# uOsc_2_board_1_v2_0.net
KiCad netlist of a schematic drawn in EAGLE
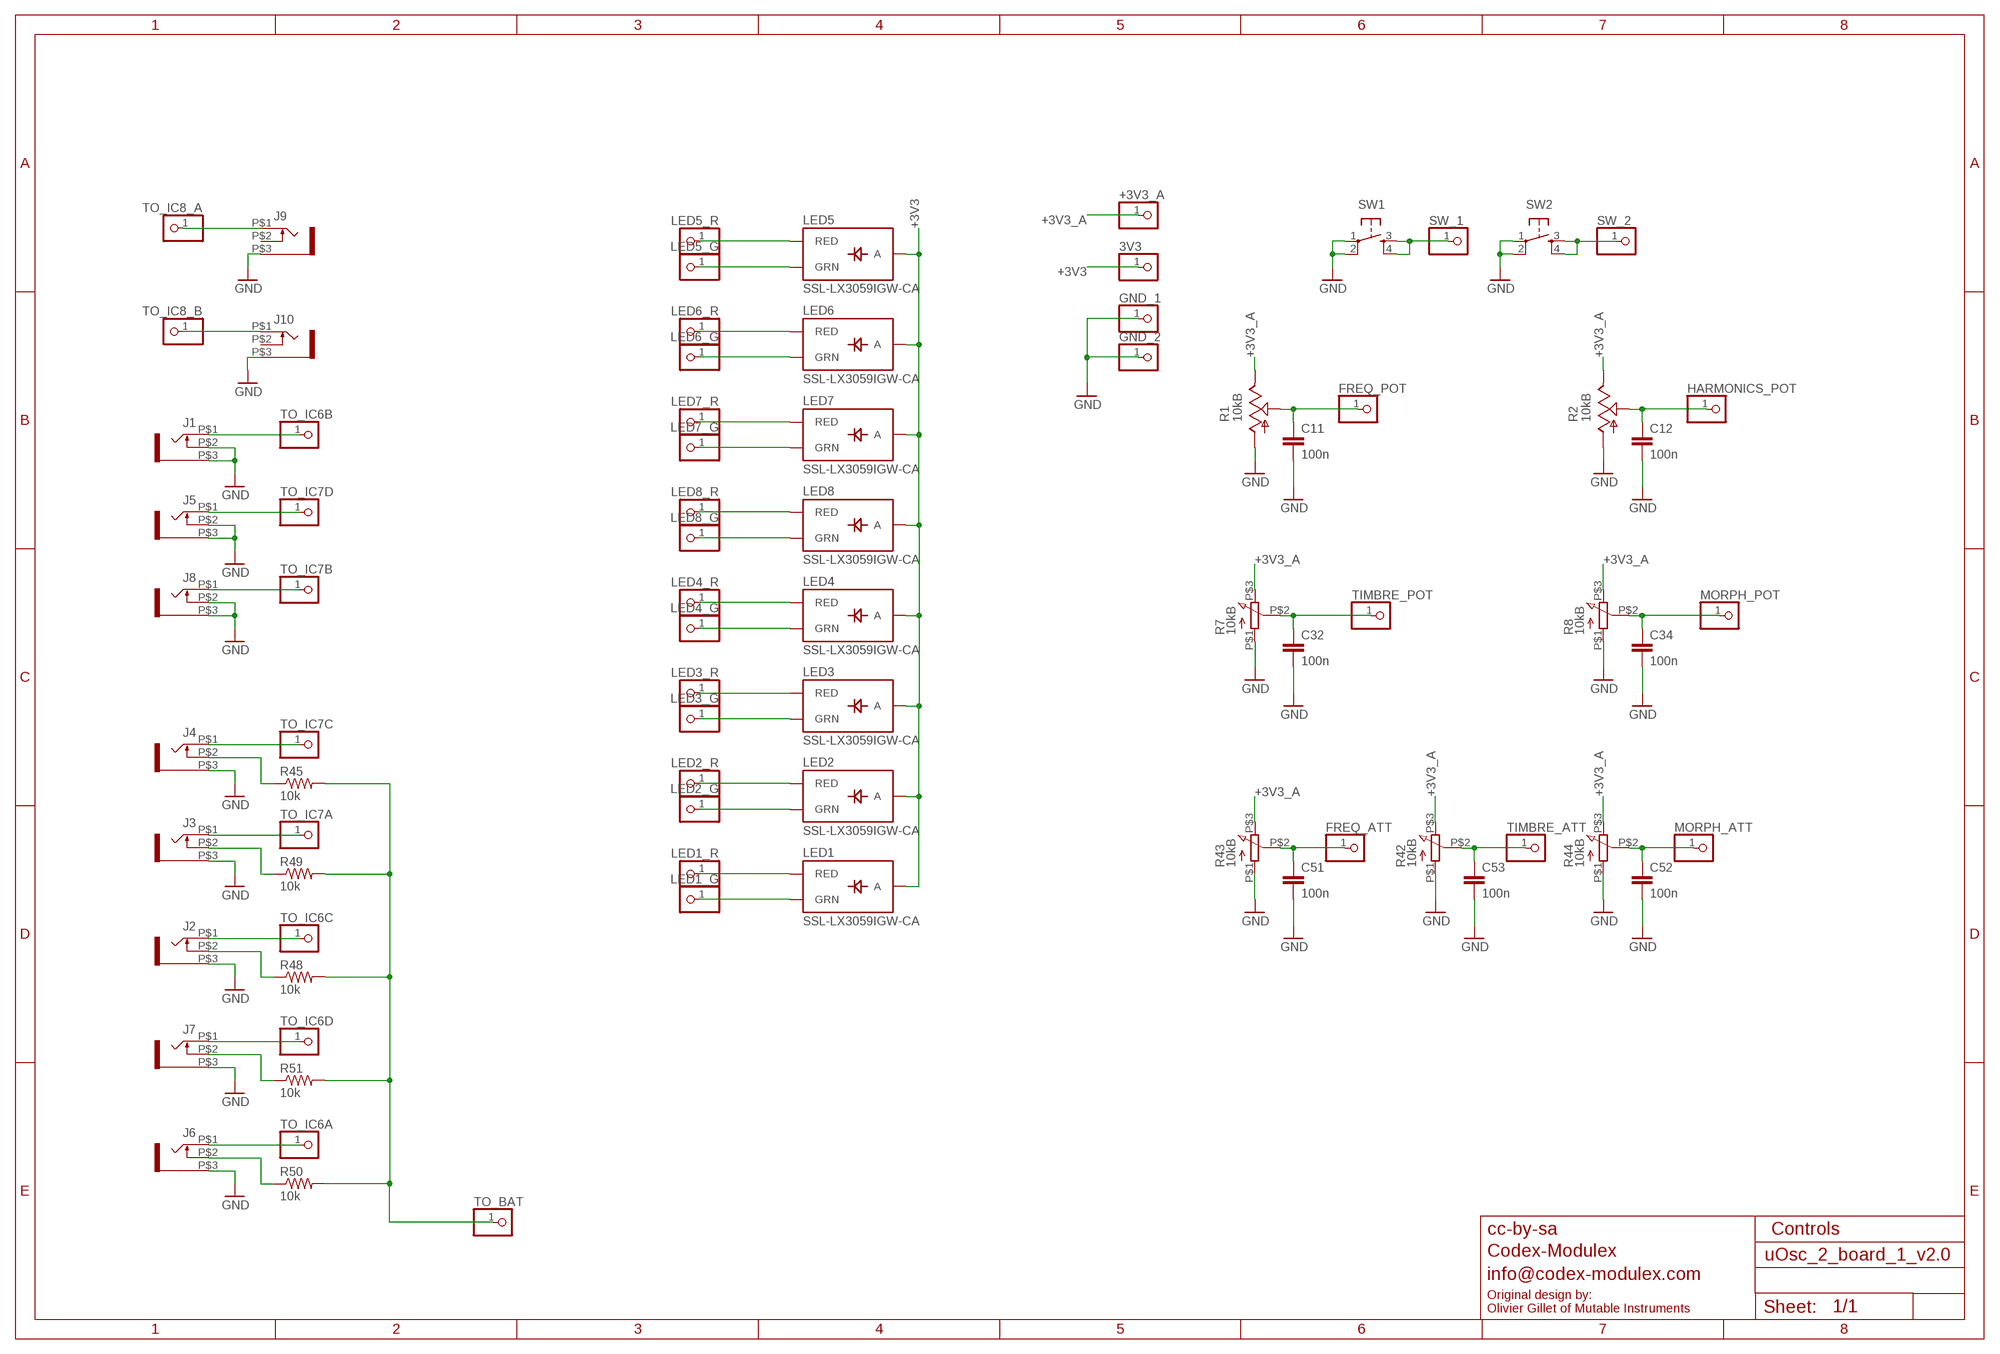
[diagram p0: schematic, sheet 1]

(export (version "E")
  (design (tool "Eeschema 10.0.6"))
  (components
    (comp (ref "+3V3_A")
      (value "PARTS_AMAN_PINHD-1X1")
      (footprint "eagle-import:PARTS_AMAN_1X01")
      (libsource (lib "eagle-import") (part "PARTS_AMAN_PINHD-1X1"))
    )
    (comp (ref "3V3")
      (value "PARTS_AMAN_PINHD-1X1")
      (footprint "eagle-import:PARTS_AMAN_1X01")
      (libsource (lib "eagle-import") (part "PARTS_AMAN_PINHD-1X1"))
    )
    (comp (ref "C11")
      (value "100n")
      (footprint "eagle-import:PARTS_AMAN_RESISTOR_0603")
      (libsource (lib "eagle-import") (part "PARTS_AMAN_CAPACITOR"))
    )
    (comp (ref "C12")
      (value "100n")
      (footprint "eagle-import:PARTS_AMAN_RESISTOR_0603")
      (libsource (lib "eagle-import") (part "PARTS_AMAN_CAPACITOR"))
    )
    (comp (ref "C32")
      (value "100n")
      (footprint "eagle-import:PARTS_AMAN_RESISTOR_0603")
      (libsource (lib "eagle-import") (part "PARTS_AMAN_CAPACITOR"))
    )
    (comp (ref "C34")
      (value "100n")
      (footprint "eagle-import:PARTS_AMAN_RESISTOR_0603")
      (libsource (lib "eagle-import") (part "PARTS_AMAN_CAPACITOR"))
    )
    (comp (ref "C51")
      (value "100n")
      (footprint "eagle-import:PARTS_AMAN_RESISTOR_0603")
      (libsource (lib "eagle-import") (part "PARTS_AMAN_CAPACITOR"))
    )
    (comp (ref "C52")
      (value "100n")
      (footprint "eagle-import:PARTS_AMAN_RESISTOR_0603")
      (libsource (lib "eagle-import") (part "PARTS_AMAN_CAPACITOR"))
    )
    (comp (ref "C53")
      (value "100n")
      (footprint "eagle-import:PARTS_AMAN_RESISTOR_0603")
      (libsource (lib "eagle-import") (part "PARTS_AMAN_CAPACITOR"))
    )
    (comp (ref "FREQ_ATT")
      (value "PARTS_AMAN_PINHD-1X1")
      (footprint "eagle-import:PARTS_AMAN_1X01")
      (libsource (lib "eagle-import") (part "PARTS_AMAN_PINHD-1X1"))
    )
    (comp (ref "FREQ_POT")
      (value "PARTS_AMAN_PINHD-1X1")
      (footprint "eagle-import:PARTS_AMAN_1X01")
      (libsource (lib "eagle-import") (part "PARTS_AMAN_PINHD-1X1"))
    )
    (comp (ref "GND_1")
      (value "PARTS_AMAN_PINHD-1X1")
      (footprint "eagle-import:PARTS_AMAN_1X01")
      (libsource (lib "eagle-import") (part "PARTS_AMAN_PINHD-1X1"))
    )
    (comp (ref "GND_2")
      (value "PARTS_AMAN_PINHD-1X1")
      (footprint "eagle-import:PARTS_AMAN_1X01")
      (libsource (lib "eagle-import") (part "PARTS_AMAN_PINHD-1X1"))
    )
    (comp (ref "HARMONICS_POT")
      (value "PARTS_AMAN_PINHD-1X1")
      (footprint "eagle-import:PARTS_AMAN_1X01")
      (libsource (lib "eagle-import") (part "PARTS_AMAN_PINHD-1X1"))
    )
    (comp (ref "J1")
      (value "WQP-PJ301M-12_JACK")
      (footprint "eagle-import:WQP-PJ301M-12_JACK")
      (libsource (lib "eagle-import") (part "WQP-PJ301M-12_JACK"))
    )
    (comp (ref "J2")
      (value "WQP-PJ301M-12_JACK")
      (footprint "eagle-import:WQP-PJ301M-12_JACK")
      (libsource (lib "eagle-import") (part "WQP-PJ301M-12_JACK"))
    )
    (comp (ref "J3")
      (value "WQP-PJ301M-12_JACK")
      (footprint "eagle-import:WQP-PJ301M-12_JACK")
      (libsource (lib "eagle-import") (part "WQP-PJ301M-12_JACK"))
    )
    (comp (ref "J4")
      (value "WQP-PJ301M-12_JACK")
      (footprint "eagle-import:WQP-PJ301M-12_JACK")
      (libsource (lib "eagle-import") (part "WQP-PJ301M-12_JACK"))
    )
    (comp (ref "J5")
      (value "WQP-PJ301M-12_JACK")
      (footprint "eagle-import:WQP-PJ301M-12_JACK")
      (libsource (lib "eagle-import") (part "WQP-PJ301M-12_JACK"))
    )
    (comp (ref "J6")
      (value "WQP-PJ301M-12_JACK")
      (footprint "eagle-import:WQP-PJ301M-12_JACK")
      (libsource (lib "eagle-import") (part "WQP-PJ301M-12_JACK"))
    )
    (comp (ref "J7")
      (value "WQP-PJ301M-12_JACK")
      (footprint "eagle-import:WQP-PJ301M-12_JACK")
      (libsource (lib "eagle-import") (part "WQP-PJ301M-12_JACK"))
    )
    (comp (ref "J8")
      (value "WQP-PJ301M-12_JACK")
      (footprint "eagle-import:WQP-PJ301M-12_JACK")
      (libsource (lib "eagle-import") (part "WQP-PJ301M-12_JACK"))
    )
    (comp (ref "J9")
      (value "WQP-PJ301M-12_JACK")
      (footprint "eagle-import:WQP-PJ301M-12_JACK")
      (libsource (lib "eagle-import") (part "WQP-PJ301M-12_JACK"))
    )
    (comp (ref "J10")
      (value "WQP-PJ301M-12_JACK")
      (footprint "eagle-import:WQP-PJ301M-12_JACK")
      (libsource (lib "eagle-import") (part "WQP-PJ301M-12_JACK"))
    )
    (comp (ref "LED1")
      (value "SSL-LX3059IGW-CA")
      (footprint "eagle-import:LED-BICOLOR-THROUGHHOLE-LUMEX")
      (libsource (lib "eagle-import") (part "LED-BICOLOR-THROUGHHOLE-CA"))
    )
    (comp (ref "LED1_G")
      (value "PARTS_AMAN_PINHD-1X1")
      (footprint "eagle-import:PARTS_AMAN_1X01")
      (libsource (lib "eagle-import") (part "PARTS_AMAN_PINHD-1X1"))
    )
    (comp (ref "LED1_R")
      (value "PARTS_AMAN_PINHD-1X1")
      (footprint "eagle-import:PARTS_AMAN_1X01")
      (libsource (lib "eagle-import") (part "PARTS_AMAN_PINHD-1X1"))
    )
    (comp (ref "LED2")
      (value "SSL-LX3059IGW-CA")
      (footprint "eagle-import:LED-BICOLOR-THROUGHHOLE-LUMEX")
      (libsource (lib "eagle-import") (part "LED-BICOLOR-THROUGHHOLE-CA"))
    )
    (comp (ref "LED2_G")
      (value "PARTS_AMAN_PINHD-1X1")
      (footprint "eagle-import:PARTS_AMAN_1X01")
      (libsource (lib "eagle-import") (part "PARTS_AMAN_PINHD-1X1"))
    )
    (comp (ref "LED2_R")
      (value "PARTS_AMAN_PINHD-1X1")
      (footprint "eagle-import:PARTS_AMAN_1X01")
      (libsource (lib "eagle-import") (part "PARTS_AMAN_PINHD-1X1"))
    )
    (comp (ref "LED3")
      (value "SSL-LX3059IGW-CA")
      (footprint "eagle-import:LED-BICOLOR-THROUGHHOLE-LUMEX")
      (libsource (lib "eagle-import") (part "LED-BICOLOR-THROUGHHOLE-CA"))
    )
    (comp (ref "LED3_G")
      (value "PARTS_AMAN_PINHD-1X1")
      (footprint "eagle-import:PARTS_AMAN_1X01")
      (libsource (lib "eagle-import") (part "PARTS_AMAN_PINHD-1X1"))
    )
    (comp (ref "LED3_R")
      (value "PARTS_AMAN_PINHD-1X1")
      (footprint "eagle-import:PARTS_AMAN_1X01")
      (libsource (lib "eagle-import") (part "PARTS_AMAN_PINHD-1X1"))
    )
    (comp (ref "LED4")
      (value "SSL-LX3059IGW-CA")
      (footprint "eagle-import:LED-BICOLOR-THROUGHHOLE-LUMEX")
      (libsource (lib "eagle-import") (part "LED-BICOLOR-THROUGHHOLE-CA"))
    )
    (comp (ref "LED4_G")
      (value "PARTS_AMAN_PINHD-1X1")
      (footprint "eagle-import:PARTS_AMAN_1X01")
      (libsource (lib "eagle-import") (part "PARTS_AMAN_PINHD-1X1"))
    )
    (comp (ref "LED4_R")
      (value "PARTS_AMAN_PINHD-1X1")
      (footprint "eagle-import:PARTS_AMAN_1X01")
      (libsource (lib "eagle-import") (part "PARTS_AMAN_PINHD-1X1"))
    )
    (comp (ref "LED5")
      (value "SSL-LX3059IGW-CA")
      (footprint "eagle-import:LED-BICOLOR-THROUGHHOLE-LUMEX")
      (libsource (lib "eagle-import") (part "LED-BICOLOR-THROUGHHOLE-CA"))
    )
    (comp (ref "LED5_G")
      (value "PARTS_AMAN_PINHD-1X1")
      (footprint "eagle-import:PARTS_AMAN_1X01")
      (libsource (lib "eagle-import") (part "PARTS_AMAN_PINHD-1X1"))
    )
    (comp (ref "LED5_R")
      (value "PARTS_AMAN_PINHD-1X1")
      (footprint "eagle-import:PARTS_AMAN_1X01")
      (libsource (lib "eagle-import") (part "PARTS_AMAN_PINHD-1X1"))
    )
    (comp (ref "LED6")
      (value "SSL-LX3059IGW-CA")
      (footprint "eagle-import:LED-BICOLOR-THROUGHHOLE-LUMEX")
      (libsource (lib "eagle-import") (part "LED-BICOLOR-THROUGHHOLE-CA"))
    )
    (comp (ref "LED6_G")
      (value "PARTS_AMAN_PINHD-1X1")
      (footprint "eagle-import:PARTS_AMAN_1X01")
      (libsource (lib "eagle-import") (part "PARTS_AMAN_PINHD-1X1"))
    )
    (comp (ref "LED6_R")
      (value "PARTS_AMAN_PINHD-1X1")
      (footprint "eagle-import:PARTS_AMAN_1X01")
      (libsource (lib "eagle-import") (part "PARTS_AMAN_PINHD-1X1"))
    )
    (comp (ref "LED7")
      (value "SSL-LX3059IGW-CA")
      (footprint "eagle-import:LED-BICOLOR-THROUGHHOLE-LUMEX")
      (libsource (lib "eagle-import") (part "LED-BICOLOR-THROUGHHOLE-CA"))
    )
    (comp (ref "LED7_G")
      (value "PARTS_AMAN_PINHD-1X1")
      (footprint "eagle-import:PARTS_AMAN_1X01")
      (libsource (lib "eagle-import") (part "PARTS_AMAN_PINHD-1X1"))
    )
    (comp (ref "LED7_R")
      (value "PARTS_AMAN_PINHD-1X1")
      (footprint "eagle-import:PARTS_AMAN_1X01")
      (libsource (lib "eagle-import") (part "PARTS_AMAN_PINHD-1X1"))
    )
    (comp (ref "LED8")
      (value "SSL-LX3059IGW-CA")
      (footprint "eagle-import:LED-BICOLOR-THROUGHHOLE-LUMEX")
      (libsource (lib "eagle-import") (part "LED-BICOLOR-THROUGHHOLE-CA"))
    )
    (comp (ref "LED8_G")
      (value "PARTS_AMAN_PINHD-1X1")
      (footprint "eagle-import:PARTS_AMAN_1X01")
      (libsource (lib "eagle-import") (part "PARTS_AMAN_PINHD-1X1"))
    )
    (comp (ref "LED8_R")
      (value "PARTS_AMAN_PINHD-1X1")
      (footprint "eagle-import:PARTS_AMAN_1X01")
      (libsource (lib "eagle-import") (part "PARTS_AMAN_PINHD-1X1"))
    )
    (comp (ref "MORPH_ATT")
      (value "PARTS_AMAN_PINHD-1X1")
      (footprint "eagle-import:PARTS_AMAN_1X01")
      (libsource (lib "eagle-import") (part "PARTS_AMAN_PINHD-1X1"))
    )
    (comp (ref "MORPH_POT")
      (value "PARTS_AMAN_PINHD-1X1")
      (footprint "eagle-import:PARTS_AMAN_1X01")
      (libsource (lib "eagle-import") (part "PARTS_AMAN_PINHD-1X1"))
    )
    (comp (ref "R1")
      (value "10kB")
      (footprint "eagle-import:ALPS_POT_VERTICAL_PS")
      (libsource (lib "eagle-import") (part "POT_USVERTICAL_PS"))
    )
    (comp (ref "R2")
      (value "10kB")
      (footprint "eagle-import:ALPS_POT_VERTICAL_PS")
      (libsource (lib "eagle-import") (part "POT_USVERTICAL_PS"))
    )
    (comp (ref "R7")
      (value "10kB")
      (footprint "eagle-import:INSTRUO_Q-POT2")
      (libsource (lib "eagle-import") (part "INSTRUO_Q-POT2"))
    )
    (comp (ref "R8")
      (value "10kB")
      (footprint "eagle-import:INSTRUO_Q-POT2")
      (libsource (lib "eagle-import") (part "INSTRUO_Q-POT2"))
    )
    (comp (ref "R42")
      (value "10kB")
      (footprint "eagle-import:INSTRUO_Q-POT2")
      (libsource (lib "eagle-import") (part "INSTRUO_Q-POT2"))
    )
    (comp (ref "R43")
      (value "10kB")
      (footprint "eagle-import:INSTRUO_Q-POT2")
      (libsource (lib "eagle-import") (part "INSTRUO_Q-POT2"))
    )
    (comp (ref "R44")
      (value "10kB")
      (footprint "eagle-import:INSTRUO_Q-POT2")
      (libsource (lib "eagle-import") (part "INSTRUO_Q-POT2"))
    )
    (comp (ref "R45")
      (value "10k")
      (footprint "eagle-import:PARTS_AMAN_RESISTOR_0603")
      (libsource (lib "eagle-import") (part "PARTS_AMAN_RESISTOR"))
    )
    (comp (ref "R48")
      (value "10k")
      (footprint "eagle-import:PARTS_AMAN_RESISTOR_0603")
      (libsource (lib "eagle-import") (part "PARTS_AMAN_RESISTOR"))
    )
    (comp (ref "R49")
      (value "10k")
      (footprint "eagle-import:PARTS_AMAN_RESISTOR_0603")
      (libsource (lib "eagle-import") (part "PARTS_AMAN_RESISTOR"))
    )
    (comp (ref "R50")
      (value "10k")
      (footprint "eagle-import:PARTS_AMAN_RESISTOR_0603")
      (libsource (lib "eagle-import") (part "PARTS_AMAN_RESISTOR"))
    )
    (comp (ref "R51")
      (value "10k")
      (footprint "eagle-import:PARTS_AMAN_RESISTOR_0603")
      (libsource (lib "eagle-import") (part "PARTS_AMAN_RESISTOR"))
    )
    (comp (ref "SW1")
      (value "TAC_SWITCHPTH")
      (footprint "eagle-import:TACTILE-PTH")
      (libsource (lib "eagle-import") (part "TAC_SWITCHPTH"))
    )
    (comp (ref "SW2")
      (value "TAC_SWITCHPTH")
      (footprint "eagle-import:TACTILE-PTH")
      (libsource (lib "eagle-import") (part "TAC_SWITCHPTH"))
    )
    (comp (ref "SW_1")
      (value "PARTS_AMAN_PINHD-1X1")
      (footprint "eagle-import:PARTS_AMAN_1X01")
      (libsource (lib "eagle-import") (part "PARTS_AMAN_PINHD-1X1"))
    )
    (comp (ref "SW_2")
      (value "PARTS_AMAN_PINHD-1X1")
      (footprint "eagle-import:PARTS_AMAN_1X01")
      (libsource (lib "eagle-import") (part "PARTS_AMAN_PINHD-1X1"))
    )
    (comp (ref "TIMBRE_ATT")
      (value "PARTS_AMAN_PINHD-1X1")
      (footprint "eagle-import:PARTS_AMAN_1X01")
      (libsource (lib "eagle-import") (part "PARTS_AMAN_PINHD-1X1"))
    )
    (comp (ref "TIMBRE_POT")
      (value "PARTS_AMAN_PINHD-1X1")
      (footprint "eagle-import:PARTS_AMAN_1X01")
      (libsource (lib "eagle-import") (part "PARTS_AMAN_PINHD-1X1"))
    )
    (comp (ref "TO_BAT")
      (value "PARTS_AMAN_PINHD-1X1")
      (footprint "eagle-import:PARTS_AMAN_1X01")
      (libsource (lib "eagle-import") (part "PARTS_AMAN_PINHD-1X1"))
    )
    (comp (ref "TO_IC6A")
      (value "PARTS_AMAN_PINHD-1X1")
      (footprint "eagle-import:PARTS_AMAN_1X01")
      (libsource (lib "eagle-import") (part "PARTS_AMAN_PINHD-1X1"))
    )
    (comp (ref "TO_IC6B")
      (value "PARTS_AMAN_PINHD-1X1")
      (footprint "eagle-import:PARTS_AMAN_1X01")
      (libsource (lib "eagle-import") (part "PARTS_AMAN_PINHD-1X1"))
    )
    (comp (ref "TO_IC6C")
      (value "PARTS_AMAN_PINHD-1X1")
      (footprint "eagle-import:PARTS_AMAN_1X01")
      (libsource (lib "eagle-import") (part "PARTS_AMAN_PINHD-1X1"))
    )
    (comp (ref "TO_IC6D")
      (value "PARTS_AMAN_PINHD-1X1")
      (footprint "eagle-import:PARTS_AMAN_1X01")
      (libsource (lib "eagle-import") (part "PARTS_AMAN_PINHD-1X1"))
    )
    (comp (ref "TO_IC7A")
      (value "PARTS_AMAN_PINHD-1X1")
      (footprint "eagle-import:PARTS_AMAN_1X01")
      (libsource (lib "eagle-import") (part "PARTS_AMAN_PINHD-1X1"))
    )
    (comp (ref "TO_IC7B")
      (value "PARTS_AMAN_PINHD-1X1")
      (footprint "eagle-import:PARTS_AMAN_1X01")
      (libsource (lib "eagle-import") (part "PARTS_AMAN_PINHD-1X1"))
    )
    (comp (ref "TO_IC7C")
      (value "PARTS_AMAN_PINHD-1X1")
      (footprint "eagle-import:PARTS_AMAN_1X01")
      (libsource (lib "eagle-import") (part "PARTS_AMAN_PINHD-1X1"))
    )
    (comp (ref "TO_IC7D")
      (value "PARTS_AMAN_PINHD-1X1")
      (footprint "eagle-import:PARTS_AMAN_1X01")
      (libsource (lib "eagle-import") (part "PARTS_AMAN_PINHD-1X1"))
    )
    (comp (ref "TO_IC8_A")
      (value "PARTS_AMAN_PINHD-1X1")
      (footprint "eagle-import:PARTS_AMAN_1X01")
      (libsource (lib "eagle-import") (part "PARTS_AMAN_PINHD-1X1"))
    )
    (comp (ref "TO_IC8_B")
      (value "PARTS_AMAN_PINHD-1X1")
      (footprint "eagle-import:PARTS_AMAN_1X01")
      (libsource (lib "eagle-import") (part "PARTS_AMAN_PINHD-1X1"))
    )
  )
  (nets
    (net (code "1") (name "/+3V3") (class "Default")
      (node (ref "3V3") (pin "1") (pinfunction "1_1") (pintype "passive"))
      (node (ref "LED1") (pin "A") (pinfunction "A_A") (pintype "bidirectional"))
      (node (ref "LED2") (pin "A") (pinfunction "A_A") (pintype "bidirectional"))
      (node (ref "LED3") (pin "A") (pinfunction "A_A") (pintype "bidirectional"))
      (node (ref "LED4") (pin "A") (pinfunction "A_A") (pintype "bidirectional"))
      (node (ref "LED5") (pin "A") (pinfunction "A_A") (pintype "bidirectional"))
      (node (ref "LED6") (pin "A") (pinfunction "A_A") (pintype "bidirectional"))
      (node (ref "LED7") (pin "A") (pinfunction "A_A") (pintype "bidirectional"))
      (node (ref "LED8") (pin "A") (pinfunction "A_A") (pintype "bidirectional"))
    )
    (net (code "2") (name "/+3V3_A") (class "Default")
      (node (ref "+3V3_A") (pin "1") (pinfunction "1_1") (pintype "passive"))
      (node (ref "R1") (pin "P$1") (pinfunction "E_P$1") (pintype "passive"))
      (node (ref "R2") (pin "P$1") (pinfunction "E_P$1") (pintype "passive"))
      (node (ref "R42") (pin "P$3") (pinfunction "3_P$3") (pintype "passive"))
      (node (ref "R43") (pin "P$3") (pinfunction "3_P$3") (pintype "passive"))
      (node (ref "R44") (pin "P$3") (pinfunction "3_P$3") (pintype "passive"))
      (node (ref "R7") (pin "P$3") (pinfunction "3_P$3") (pintype "passive"))
      (node (ref "R8") (pin "P$3") (pinfunction "3_P$3") (pintype "passive"))
    )
    (net (code "3") (name "GND") (class "Default")
      (node (ref "C11") (pin "2") (pinfunction "2_2") (pintype "passive"))
      (node (ref "C12") (pin "2") (pinfunction "2_2") (pintype "passive"))
      (node (ref "C32") (pin "2") (pinfunction "2_2") (pintype "passive"))
      (node (ref "C34") (pin "2") (pinfunction "2_2") (pintype "passive"))
      (node (ref "C51") (pin "2") (pinfunction "2_2") (pintype "passive"))
      (node (ref "C52") (pin "2") (pinfunction "2_2") (pintype "passive"))
      (node (ref "C53") (pin "2") (pinfunction "2_2") (pintype "passive"))
      (node (ref "GND_1") (pin "1") (pinfunction "1_1") (pintype "passive"))
      (node (ref "GND_2") (pin "1") (pinfunction "1_1") (pintype "passive"))
      (node (ref "J1") (pin "P$2") (pinfunction "3_P$2") (pintype "passive"))
      (node (ref "J1") (pin "P$3") (pinfunction "1_P$3") (pintype "passive"))
      (node (ref "J10") (pin "P$3") (pinfunction "1_P$3") (pintype "passive"))
      (node (ref "J2") (pin "P$3") (pinfunction "1_P$3") (pintype "passive"))
      (node (ref "J3") (pin "P$3") (pinfunction "1_P$3") (pintype "passive"))
      (node (ref "J4") (pin "P$3") (pinfunction "1_P$3") (pintype "passive"))
      (node (ref "J5") (pin "P$2") (pinfunction "3_P$2") (pintype "passive"))
      (node (ref "J5") (pin "P$3") (pinfunction "1_P$3") (pintype "passive"))
      (node (ref "J6") (pin "P$3") (pinfunction "1_P$3") (pintype "passive"))
      (node (ref "J7") (pin "P$3") (pinfunction "1_P$3") (pintype "passive"))
      (node (ref "J8") (pin "P$2") (pinfunction "3_P$2") (pintype "passive"))
      (node (ref "J8") (pin "P$3") (pinfunction "1_P$3") (pintype "passive"))
      (node (ref "J9") (pin "P$3") (pinfunction "1_P$3") (pintype "passive"))
      (node (ref "R1") (pin "P$3") (pinfunction "A_P$3") (pintype "passive"))
      (node (ref "R2") (pin "P$3") (pinfunction "A_P$3") (pintype "passive"))
      (node (ref "R42") (pin "P$1") (pinfunction "1_P$1") (pintype "passive"))
      (node (ref "R43") (pin "P$1") (pinfunction "1_P$1") (pintype "passive"))
      (node (ref "R44") (pin "P$1") (pinfunction "1_P$1") (pintype "passive"))
      (node (ref "R7") (pin "P$1") (pinfunction "1_P$1") (pintype "passive"))
      (node (ref "R8") (pin "P$1") (pinfunction "1_P$1") (pintype "passive"))
      (node (ref "SW1") (pin "1") (pinfunction "1_1") (pintype "passive"))
      (node (ref "SW1") (pin "2") (pinfunction "2_2") (pintype "passive"))
      (node (ref "SW2") (pin "1") (pinfunction "1_1") (pintype "passive"))
      (node (ref "SW2") (pin "2") (pinfunction "2_2") (pintype "passive"))
    )
    (net (code "4") (name "Net-(J1-2)") (class "Default")
      (node (ref "J1") (pin "P$1") (pinfunction "2_P$1") (pintype "passive"))
      (node (ref "TO_IC6B") (pin "1") (pinfunction "1_1") (pintype "passive"))
    )
    (net (code "5") (name "Net-(J2-2)") (class "Default")
      (node (ref "J2") (pin "P$1") (pinfunction "2_P$1") (pintype "passive"))
      (node (ref "TO_IC6C") (pin "1") (pinfunction "1_1") (pintype "passive"))
    )
    (net (code "6") (name "Net-(J2-3)") (class "Default")
      (node (ref "J2") (pin "P$2") (pinfunction "3_P$2") (pintype "passive"))
      (node (ref "R48") (pin "1") (pinfunction "1_1") (pintype "passive"))
    )
    (net (code "7") (name "Net-(J3-2)") (class "Default")
      (node (ref "J3") (pin "P$1") (pinfunction "2_P$1") (pintype "passive"))
      (node (ref "TO_IC7A") (pin "1") (pinfunction "1_1") (pintype "passive"))
    )
    (net (code "8") (name "Net-(J3-3)") (class "Default")
      (node (ref "J3") (pin "P$2") (pinfunction "3_P$2") (pintype "passive"))
      (node (ref "R49") (pin "1") (pinfunction "1_1") (pintype "passive"))
    )
    (net (code "9") (name "Net-(J4-2)") (class "Default")
      (node (ref "J4") (pin "P$1") (pinfunction "2_P$1") (pintype "passive"))
      (node (ref "TO_IC7C") (pin "1") (pinfunction "1_1") (pintype "passive"))
    )
    (net (code "10") (name "Net-(J4-3)") (class "Default")
      (node (ref "J4") (pin "P$2") (pinfunction "3_P$2") (pintype "passive"))
      (node (ref "R45") (pin "1") (pinfunction "1_1") (pintype "passive"))
    )
    (net (code "11") (name "Net-(J5-2)") (class "Default")
      (node (ref "J5") (pin "P$1") (pinfunction "2_P$1") (pintype "passive"))
      (node (ref "TO_IC7D") (pin "1") (pinfunction "1_1") (pintype "passive"))
    )
    (net (code "12") (name "Net-(J6-2)") (class "Default")
      (node (ref "J6") (pin "P$1") (pinfunction "2_P$1") (pintype "passive"))
      (node (ref "TO_IC6A") (pin "1") (pinfunction "1_1") (pintype "passive"))
    )
    (net (code "13") (name "Net-(J6-3)") (class "Default")
      (node (ref "J6") (pin "P$2") (pinfunction "3_P$2") (pintype "passive"))
      (node (ref "R50") (pin "1") (pinfunction "1_1") (pintype "passive"))
    )
    (net (code "14") (name "Net-(J7-2)") (class "Default")
      (node (ref "J7") (pin "P$1") (pinfunction "2_P$1") (pintype "passive"))
      (node (ref "TO_IC6D") (pin "1") (pinfunction "1_1") (pintype "passive"))
    )
    (net (code "15") (name "Net-(J7-3)") (class "Default")
      (node (ref "J7") (pin "P$2") (pinfunction "3_P$2") (pintype "passive"))
      (node (ref "R51") (pin "1") (pinfunction "1_1") (pintype "passive"))
    )
    (net (code "16") (name "Net-(J8-2)") (class "Default")
      (node (ref "J8") (pin "P$1") (pinfunction "2_P$1") (pintype "passive"))
      (node (ref "TO_IC7B") (pin "1") (pinfunction "1_1") (pintype "passive"))
    )
    (net (code "17") (name "Net-(J9-2)") (class "Default")
      (node (ref "J9") (pin "P$1") (pinfunction "2_P$1") (pintype "passive"))
      (node (ref "TO_IC8_A") (pin "1") (pinfunction "1_1") (pintype "passive"))
    )
    (net (code "18") (name "Net-(J10-2)") (class "Default")
      (node (ref "J10") (pin "P$1") (pinfunction "2_P$1") (pintype "passive"))
      (node (ref "TO_IC8_B") (pin "1") (pinfunction "1_1") (pintype "passive"))
    )
    (net (code "19") (name "Net-(LED1-GRN)") (class "Default")
      (node (ref "LED1") (pin "GREEN_C") (pinfunction "GRN_GREEN_C") (pintype "bidirectional"))
      (node (ref "LED1_G") (pin "1") (pinfunction "1_1") (pintype "passive"))
    )
    (net (code "20") (name "Net-(LED1-RED)") (class "Default")
      (node (ref "LED1") (pin "RED_C") (pinfunction "RED_RED_C") (pintype "bidirectional"))
      (node (ref "LED1_R") (pin "1") (pinfunction "1_1") (pintype "passive"))
    )
    (net (code "21") (name "Net-(LED2-GRN)") (class "Default")
      (node (ref "LED2") (pin "GREEN_C") (pinfunction "GRN_GREEN_C") (pintype "bidirectional"))
      (node (ref "LED2_G") (pin "1") (pinfunction "1_1") (pintype "passive"))
    )
    (net (code "22") (name "Net-(LED2-RED)") (class "Default")
      (node (ref "LED2") (pin "RED_C") (pinfunction "RED_RED_C") (pintype "bidirectional"))
      (node (ref "LED2_R") (pin "1") (pinfunction "1_1") (pintype "passive"))
    )
    (net (code "23") (name "Net-(LED3-GRN)") (class "Default")
      (node (ref "LED3") (pin "GREEN_C") (pinfunction "GRN_GREEN_C") (pintype "bidirectional"))
      (node (ref "LED3_G") (pin "1") (pinfunction "1_1") (pintype "passive"))
    )
    (net (code "24") (name "Net-(LED3-RED)") (class "Default")
      (node (ref "LED3") (pin "RED_C") (pinfunction "RED_RED_C") (pintype "bidirectional"))
      (node (ref "LED3_R") (pin "1") (pinfunction "1_1") (pintype "passive"))
    )
    (net (code "25") (name "Net-(LED4-GRN)") (class "Default")
      (node (ref "LED4") (pin "GREEN_C") (pinfunction "GRN_GREEN_C") (pintype "bidirectional"))
      (node (ref "LED4_G") (pin "1") (pinfunction "1_1") (pintype "passive"))
    )
    (net (code "26") (name "Net-(LED4-RED)") (class "Default")
      (node (ref "LED4") (pin "RED_C") (pinfunction "RED_RED_C") (pintype "bidirectional"))
      (node (ref "LED4_R") (pin "1") (pinfunction "1_1") (pintype "passive"))
    )
    (net (code "27") (name "Net-(LED5-GRN)") (class "Default")
      (node (ref "LED5") (pin "GREEN_C") (pinfunction "GRN_GREEN_C") (pintype "bidirectional"))
      (node (ref "LED5_G") (pin "1") (pinfunction "1_1") (pintype "passive"))
    )
    (net (code "28") (name "Net-(LED5-RED)") (class "Default")
      (node (ref "LED5") (pin "RED_C") (pinfunction "RED_RED_C") (pintype "bidirectional"))
      (node (ref "LED5_R") (pin "1") (pinfunction "1_1") (pintype "passive"))
    )
    (net (code "29") (name "Net-(LED6-GRN)") (class "Default")
      (node (ref "LED6") (pin "GREEN_C") (pinfunction "GRN_GREEN_C") (pintype "bidirectional"))
      (node (ref "LED6_G") (pin "1") (pinfunction "1_1") (pintype "passive"))
    )
    (net (code "30") (name "Net-(LED6-RED)") (class "Default")
      (node (ref "LED6") (pin "RED_C") (pinfunction "RED_RED_C") (pintype "bidirectional"))
      (node (ref "LED6_R") (pin "1") (pinfunction "1_1") (pintype "passive"))
    )
    (net (code "31") (name "Net-(LED7-GRN)") (class "Default")
      (node (ref "LED7") (pin "GREEN_C") (pinfunction "GRN_GREEN_C") (pintype "bidirectional"))
      (node (ref "LED7_G") (pin "1") (pinfunction "1_1") (pintype "passive"))
    )
    (net (code "32") (name "Net-(LED7-RED)") (class "Default")
      (node (ref "LED7") (pin "RED_C") (pinfunction "RED_RED_C") (pintype "bidirectional"))
      (node (ref "LED7_R") (pin "1") (pinfunction "1_1") (pintype "passive"))
    )
    (net (code "33") (name "Net-(LED8-GRN)") (class "Default")
      (node (ref "LED8") (pin "GREEN_C") (pinfunction "GRN_GREEN_C") (pintype "bidirectional"))
      (node (ref "LED8_G") (pin "1") (pinfunction "1_1") (pintype "passive"))
    )
    (net (code "34") (name "Net-(LED8-RED)") (class "Default")
      (node (ref "LED8") (pin "RED_C") (pinfunction "RED_RED_C") (pintype "bidirectional"))
      (node (ref "LED8_R") (pin "1") (pinfunction "1_1") (pintype "passive"))
    )
    (net (code "35") (name "Net-(R1-S)") (class "Default")
      (node (ref "C11") (pin "1") (pinfunction "1_1") (pintype "passive"))
      (node (ref "FREQ_POT") (pin "1") (pinfunction "1_1") (pintype "passive"))
      (node (ref "R1") (pin "P$2") (pinfunction "S_P$2") (pintype "passive"))
    )
    (net (code "36") (name "Net-(R2-S)") (class "Default")
      (node (ref "C12") (pin "1") (pinfunction "1_1") (pintype "passive"))
      (node (ref "HARMONICS_POT") (pin "1") (pinfunction "1_1") (pintype "passive"))
      (node (ref "R2") (pin "P$2") (pinfunction "S_P$2") (pintype "passive"))
    )
    (net (code "37") (name "Net-(R7-2)") (class "Default")
      (node (ref "C32") (pin "1") (pinfunction "1_1") (pintype "passive"))
      (node (ref "R7") (pin "P$2") (pinfunction "2_P$2") (pintype "passive"))
      (node (ref "TIMBRE_POT") (pin "1") (pinfunction "1_1") (pintype "passive"))
    )
    (net (code "38") (name "Net-(R8-2)") (class "Default")
      (node (ref "C34") (pin "1") (pinfunction "1_1") (pintype "passive"))
      (node (ref "MORPH_POT") (pin "1") (pinfunction "1_1") (pintype "passive"))
      (node (ref "R8") (pin "P$2") (pinfunction "2_P$2") (pintype "passive"))
    )
    (net (code "39") (name "Net-(R42-2)") (class "Default")
      (node (ref "C53") (pin "1") (pinfunction "1_1") (pintype "passive"))
      (node (ref "R42") (pin "P$2") (pinfunction "2_P$2") (pintype "passive"))
      (node (ref "TIMBRE_ATT") (pin "1") (pinfunction "1_1") (pintype "passive"))
    )
    (net (code "40") (name "Net-(R43-2)") (class "Default")
      (node (ref "C51") (pin "1") (pinfunction "1_1") (pintype "passive"))
      (node (ref "FREQ_ATT") (pin "1") (pinfunction "1_1") (pintype "passive"))
      (node (ref "R43") (pin "P$2") (pinfunction "2_P$2") (pintype "passive"))
    )
    (net (code "41") (name "Net-(R44-2)") (class "Default")
      (node (ref "C52") (pin "1") (pinfunction "1_1") (pintype "passive"))
      (node (ref "MORPH_ATT") (pin "1") (pinfunction "1_1") (pintype "passive"))
      (node (ref "R44") (pin "P$2") (pinfunction "2_P$2") (pintype "passive"))
    )
    (net (code "42") (name "Net-(R45-Pad2)") (class "Default")
      (node (ref "R45") (pin "2") (pinfunction "2_2") (pintype "passive"))
      (node (ref "R48") (pin "2") (pinfunction "2_2") (pintype "passive"))
      (node (ref "R49") (pin "2") (pinfunction "2_2") (pintype "passive"))
      (node (ref "R50") (pin "2") (pinfunction "2_2") (pintype "passive"))
      (node (ref "R51") (pin "2") (pinfunction "2_2") (pintype "passive"))
      (node (ref "TO_BAT") (pin "1") (pinfunction "1_1") (pintype "passive"))
    )
    (net (code "43") (name "Net-(SW1-Pad3)") (class "Default")
      (node (ref "SW1") (pin "3") (pinfunction "3_3") (pintype "passive"))
      (node (ref "SW1") (pin "4") (pinfunction "4_4") (pintype "passive"))
      (node (ref "SW_1") (pin "1") (pinfunction "1_1") (pintype "passive"))
    )
    (net (code "44") (name "Net-(SW2-Pad3)") (class "Default")
      (node (ref "SW2") (pin "3") (pinfunction "3_3") (pintype "passive"))
      (node (ref "SW2") (pin "4") (pinfunction "4_4") (pintype "passive"))
      (node (ref "SW_2") (pin "1") (pinfunction "1_1") (pintype "passive"))
    )
    (net (code "45") (name "unconnected-(J9-3-PadP$2)") (class "Default")
      (node (ref "J9") (pin "P$2") (pinfunction "3_P$2") (pintype "passive"))
    )
    (net (code "46") (name "unconnected-(J10-3-PadP$2)") (class "Default")
      (node (ref "J10") (pin "P$2") (pinfunction "3_P$2") (pintype "passive"))
    )
  )
)
